# HexTo7seg.net
KiCad netlist of a schematic drawn in EAGLE
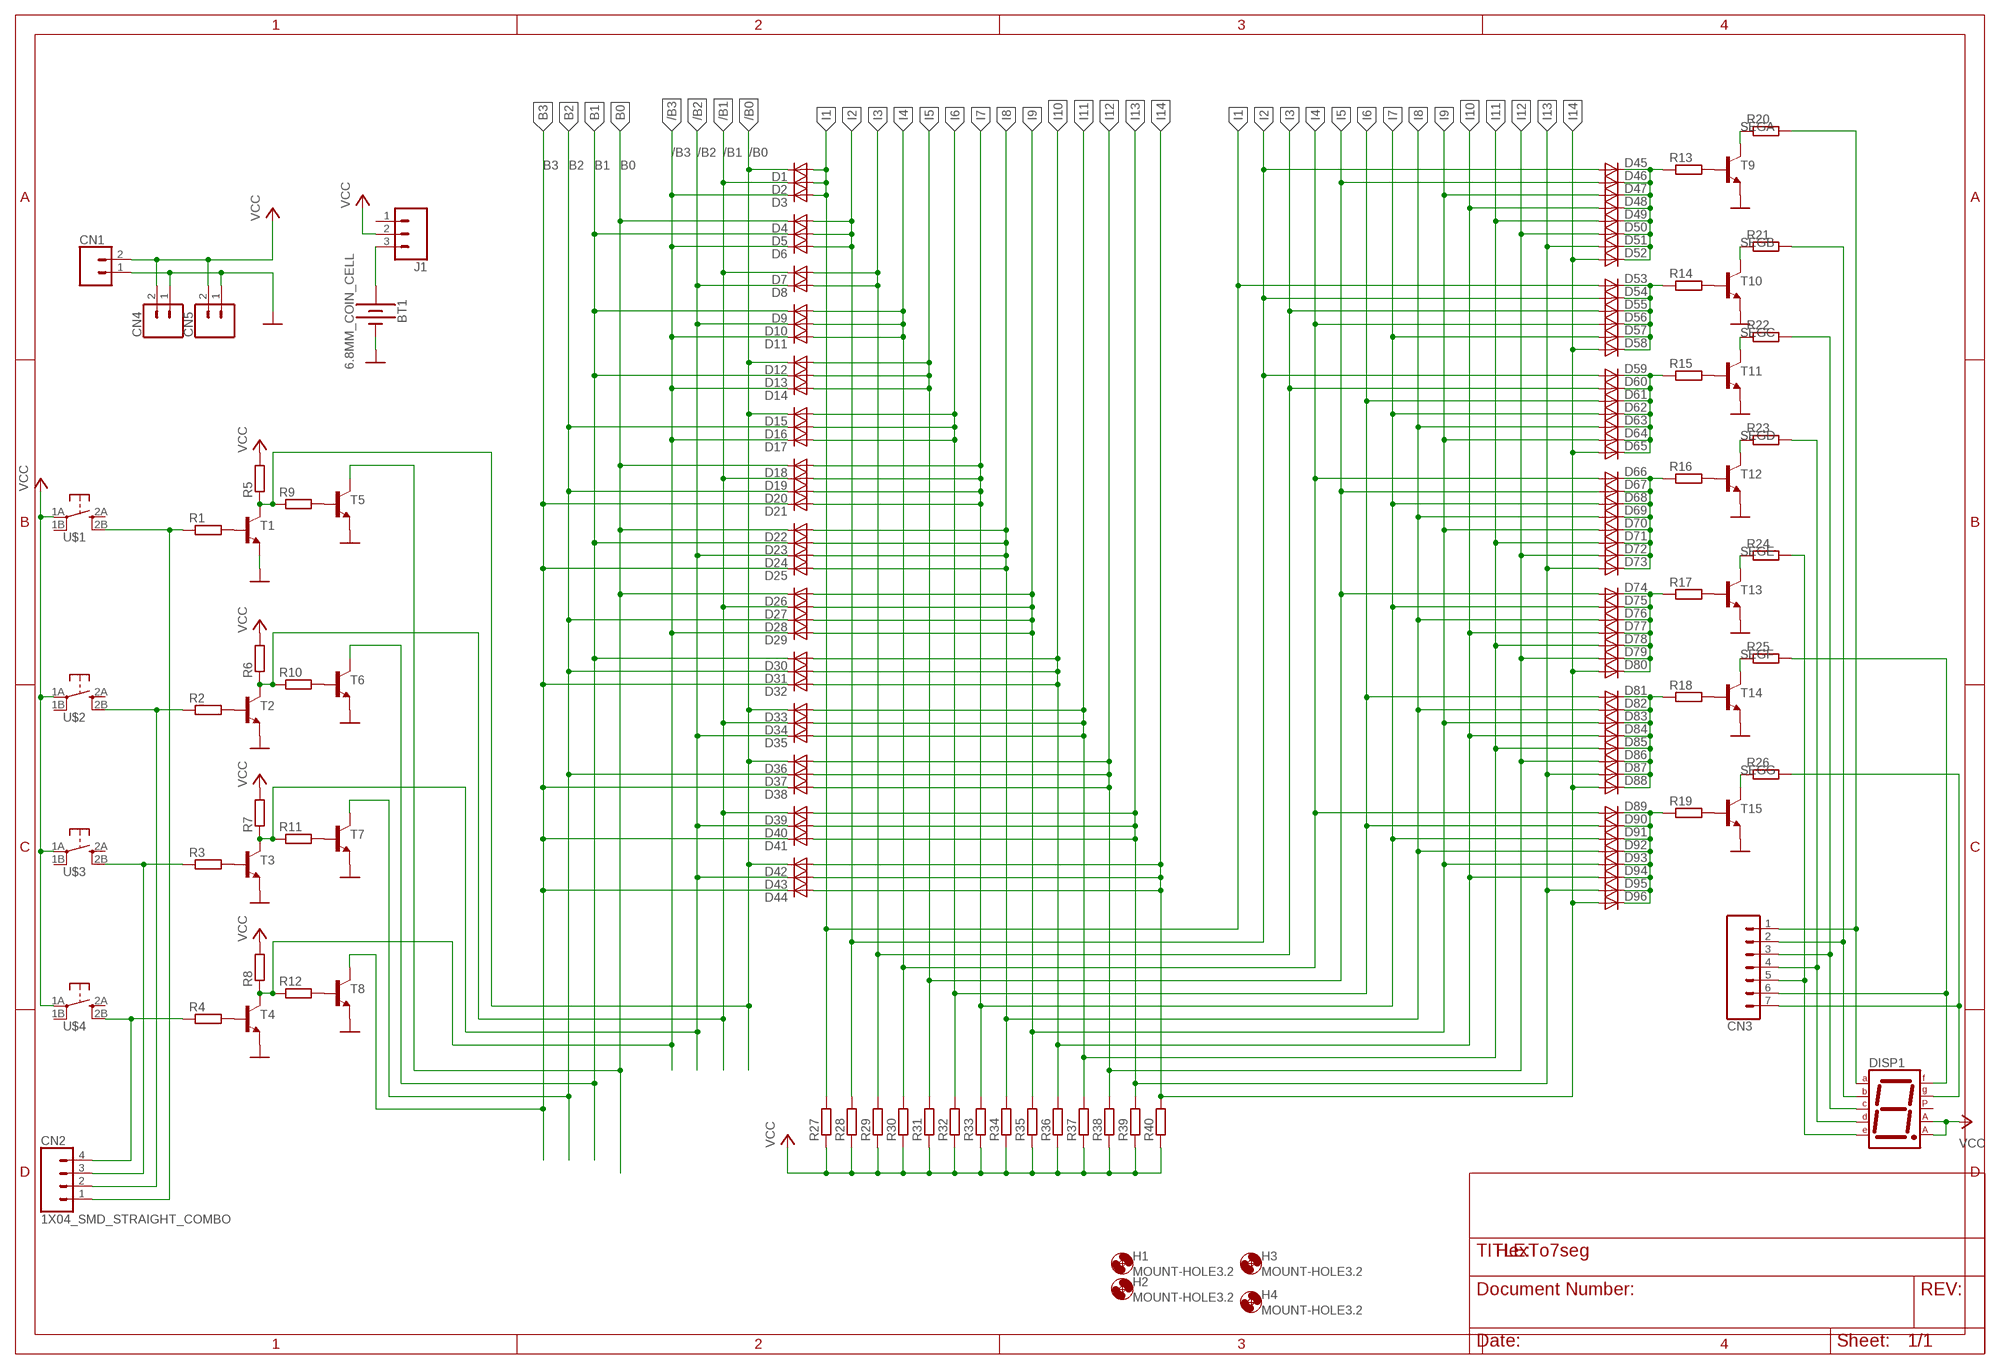
[diagram p0: schematic, sheet 1]

(export (version "E")
  (design (tool "Eeschema 10.0.6"))
  (components
    (comp (ref "BT1")
      (value "6.8MM_COIN_CELL")
      (footprint "eagle-import:BATTCOM_20MM_PTH")
      (libsource (lib "eagle-import") (part "BATTERY-20MM_PTH"))
    )
    (comp (ref "CN1")
      (value "CONN_02")
      (footprint "eagle-import:1X02")
      (libsource (lib "eagle-import") (part "CONN_02"))
    )
    (comp (ref "CN2")
      (value "1X04_SMD_STRAIGHT_COMBO")
      (footprint "eagle-import:1X04")
      (libsource (lib "eagle-import") (part "CONN_04"))
    )
    (comp (ref "CN3")
      (value "CONN_07")
      (footprint "eagle-import:1X07")
      (libsource (lib "eagle-import") (part "CONN_07"))
    )
    (comp (ref "CN4")
      (value "CONN_02")
      (footprint "eagle-import:1X02")
      (libsource (lib "eagle-import") (part "CONN_02"))
    )
    (comp (ref "CN5")
      (value "CONN_02")
      (footprint "eagle-import:1X02")
      (libsource (lib "eagle-import") (part "CONN_02"))
    )
    (comp (ref "D1")
      (value "SMALL_DIODEDO35-7")
      (footprint "eagle-import:DO35-7")
      (libsource (lib "eagle-import") (part "SMALL_DIODEDO35-7"))
    )
    (comp (ref "D2")
      (value "SMALL_DIODEDO35-7")
      (footprint "eagle-import:DO35-7")
      (libsource (lib "eagle-import") (part "SMALL_DIODEDO35-7"))
    )
    (comp (ref "D3")
      (value "SMALL_DIODEDO35-7")
      (footprint "eagle-import:DO35-7")
      (libsource (lib "eagle-import") (part "SMALL_DIODEDO35-7"))
    )
    (comp (ref "D4")
      (value "SMALL_DIODEDO35-7")
      (footprint "eagle-import:DO35-7")
      (libsource (lib "eagle-import") (part "SMALL_DIODEDO35-7"))
    )
    (comp (ref "D5")
      (value "SMALL_DIODEDO35-7")
      (footprint "eagle-import:DO35-7")
      (libsource (lib "eagle-import") (part "SMALL_DIODEDO35-7"))
    )
    (comp (ref "D6")
      (value "SMALL_DIODEDO35-7")
      (footprint "eagle-import:DO35-7")
      (libsource (lib "eagle-import") (part "SMALL_DIODEDO35-7"))
    )
    (comp (ref "D7")
      (value "SMALL_DIODEDO35-7")
      (footprint "eagle-import:DO35-7")
      (libsource (lib "eagle-import") (part "SMALL_DIODEDO35-7"))
    )
    (comp (ref "D8")
      (value "SMALL_DIODEDO35-7")
      (footprint "eagle-import:DO35-7")
      (libsource (lib "eagle-import") (part "SMALL_DIODEDO35-7"))
    )
    (comp (ref "D9")
      (value "SMALL_DIODEDO35-7")
      (footprint "eagle-import:DO35-7")
      (libsource (lib "eagle-import") (part "SMALL_DIODEDO35-7"))
    )
    (comp (ref "D10")
      (value "SMALL_DIODEDO35-7")
      (footprint "eagle-import:DO35-7")
      (libsource (lib "eagle-import") (part "SMALL_DIODEDO35-7"))
    )
    (comp (ref "D11")
      (value "SMALL_DIODEDO35-7")
      (footprint "eagle-import:DO35-7")
      (libsource (lib "eagle-import") (part "SMALL_DIODEDO35-7"))
    )
    (comp (ref "D12")
      (value "SMALL_DIODEDO35-7")
      (footprint "eagle-import:DO35-7")
      (libsource (lib "eagle-import") (part "SMALL_DIODEDO35-7"))
    )
    (comp (ref "D13")
      (value "SMALL_DIODEDO35-7")
      (footprint "eagle-import:DO35-7")
      (libsource (lib "eagle-import") (part "SMALL_DIODEDO35-7"))
    )
    (comp (ref "D14")
      (value "SMALL_DIODEDO35-7")
      (footprint "eagle-import:DO35-7")
      (libsource (lib "eagle-import") (part "SMALL_DIODEDO35-7"))
    )
    (comp (ref "D15")
      (value "SMALL_DIODEDO35-7")
      (footprint "eagle-import:DO35-7")
      (libsource (lib "eagle-import") (part "SMALL_DIODEDO35-7"))
    )
    (comp (ref "D16")
      (value "SMALL_DIODEDO35-7")
      (footprint "eagle-import:DO35-7")
      (libsource (lib "eagle-import") (part "SMALL_DIODEDO35-7"))
    )
    (comp (ref "D17")
      (value "SMALL_DIODEDO35-7")
      (footprint "eagle-import:DO35-7")
      (libsource (lib "eagle-import") (part "SMALL_DIODEDO35-7"))
    )
    (comp (ref "D18")
      (value "SMALL_DIODEDO35-7")
      (footprint "eagle-import:DO35-7")
      (libsource (lib "eagle-import") (part "SMALL_DIODEDO35-7"))
    )
    (comp (ref "D19")
      (value "SMALL_DIODEDO35-7")
      (footprint "eagle-import:DO35-7")
      (libsource (lib "eagle-import") (part "SMALL_DIODEDO35-7"))
    )
    (comp (ref "D20")
      (value "SMALL_DIODEDO35-7")
      (footprint "eagle-import:DO35-7")
      (libsource (lib "eagle-import") (part "SMALL_DIODEDO35-7"))
    )
    (comp (ref "D21")
      (value "SMALL_DIODEDO35-7")
      (footprint "eagle-import:DO35-7")
      (libsource (lib "eagle-import") (part "SMALL_DIODEDO35-7"))
    )
    (comp (ref "D22")
      (value "SMALL_DIODEDO35-7")
      (footprint "eagle-import:DO35-7")
      (libsource (lib "eagle-import") (part "SMALL_DIODEDO35-7"))
    )
    (comp (ref "D23")
      (value "SMALL_DIODEDO35-7")
      (footprint "eagle-import:DO35-7")
      (libsource (lib "eagle-import") (part "SMALL_DIODEDO35-7"))
    )
    (comp (ref "D24")
      (value "SMALL_DIODEDO35-7")
      (footprint "eagle-import:DO35-7")
      (libsource (lib "eagle-import") (part "SMALL_DIODEDO35-7"))
    )
    (comp (ref "D25")
      (value "SMALL_DIODEDO35-7")
      (footprint "eagle-import:DO35-7")
      (libsource (lib "eagle-import") (part "SMALL_DIODEDO35-7"))
    )
    (comp (ref "D26")
      (value "SMALL_DIODEDO35-7")
      (footprint "eagle-import:DO35-7")
      (libsource (lib "eagle-import") (part "SMALL_DIODEDO35-7"))
    )
    (comp (ref "D27")
      (value "SMALL_DIODEDO35-7")
      (footprint "eagle-import:DO35-7")
      (libsource (lib "eagle-import") (part "SMALL_DIODEDO35-7"))
    )
    (comp (ref "D28")
      (value "SMALL_DIODEDO35-7")
      (footprint "eagle-import:DO35-7")
      (libsource (lib "eagle-import") (part "SMALL_DIODEDO35-7"))
    )
    (comp (ref "D29")
      (value "SMALL_DIODEDO35-7")
      (footprint "eagle-import:DO35-7")
      (libsource (lib "eagle-import") (part "SMALL_DIODEDO35-7"))
    )
    (comp (ref "D30")
      (value "SMALL_DIODEDO35-7")
      (footprint "eagle-import:DO35-7")
      (libsource (lib "eagle-import") (part "SMALL_DIODEDO35-7"))
    )
    (comp (ref "D31")
      (value "SMALL_DIODEDO35-7")
      (footprint "eagle-import:DO35-7")
      (libsource (lib "eagle-import") (part "SMALL_DIODEDO35-7"))
    )
    (comp (ref "D32")
      (value "SMALL_DIODEDO35-7")
      (footprint "eagle-import:DO35-7")
      (libsource (lib "eagle-import") (part "SMALL_DIODEDO35-7"))
    )
    (comp (ref "D33")
      (value "SMALL_DIODEDO35-7")
      (footprint "eagle-import:DO35-7")
      (libsource (lib "eagle-import") (part "SMALL_DIODEDO35-7"))
    )
    (comp (ref "D34")
      (value "SMALL_DIODEDO35-7")
      (footprint "eagle-import:DO35-7")
      (libsource (lib "eagle-import") (part "SMALL_DIODEDO35-7"))
    )
    (comp (ref "D35")
      (value "SMALL_DIODEDO35-7")
      (footprint "eagle-import:DO35-7")
      (libsource (lib "eagle-import") (part "SMALL_DIODEDO35-7"))
    )
    (comp (ref "D36")
      (value "SMALL_DIODEDO35-7")
      (footprint "eagle-import:DO35-7")
      (libsource (lib "eagle-import") (part "SMALL_DIODEDO35-7"))
    )
    (comp (ref "D37")
      (value "SMALL_DIODEDO35-7")
      (footprint "eagle-import:DO35-7")
      (libsource (lib "eagle-import") (part "SMALL_DIODEDO35-7"))
    )
    (comp (ref "D38")
      (value "SMALL_DIODEDO35-7")
      (footprint "eagle-import:DO35-7")
      (libsource (lib "eagle-import") (part "SMALL_DIODEDO35-7"))
    )
    (comp (ref "D39")
      (value "SMALL_DIODEDO35-7")
      (footprint "eagle-import:DO35-7")
      (libsource (lib "eagle-import") (part "SMALL_DIODEDO35-7"))
    )
    (comp (ref "D40")
      (value "SMALL_DIODEDO35-7")
      (footprint "eagle-import:DO35-7")
      (libsource (lib "eagle-import") (part "SMALL_DIODEDO35-7"))
    )
    (comp (ref "D41")
      (value "SMALL_DIODEDO35-7")
      (footprint "eagle-import:DO35-7")
      (libsource (lib "eagle-import") (part "SMALL_DIODEDO35-7"))
    )
    (comp (ref "D42")
      (value "SMALL_DIODEDO35-7")
      (footprint "eagle-import:DO35-7")
      (libsource (lib "eagle-import") (part "SMALL_DIODEDO35-7"))
    )
    (comp (ref "D43")
      (value "SMALL_DIODEDO35-7")
      (footprint "eagle-import:DO35-7")
      (libsource (lib "eagle-import") (part "SMALL_DIODEDO35-7"))
    )
    (comp (ref "D44")
      (value "SMALL_DIODEDO35-7")
      (footprint "eagle-import:DO35-7")
      (libsource (lib "eagle-import") (part "SMALL_DIODEDO35-7"))
    )
    (comp (ref "D45")
      (value "SMALL_DIODEDO35-7")
      (footprint "eagle-import:DO35-7")
      (libsource (lib "eagle-import") (part "SMALL_DIODEDO35-7"))
    )
    (comp (ref "D46")
      (value "SMALL_DIODEDO35-7")
      (footprint "eagle-import:DO35-7")
      (libsource (lib "eagle-import") (part "SMALL_DIODEDO35-7"))
    )
    (comp (ref "D47")
      (value "SMALL_DIODEDO35-7")
      (footprint "eagle-import:DO35-7")
      (libsource (lib "eagle-import") (part "SMALL_DIODEDO35-7"))
    )
    (comp (ref "D48")
      (value "SMALL_DIODEDO35-7")
      (footprint "eagle-import:DO35-7")
      (libsource (lib "eagle-import") (part "SMALL_DIODEDO35-7"))
    )
    (comp (ref "D49")
      (value "SMALL_DIODEDO35-7")
      (footprint "eagle-import:DO35-7")
      (libsource (lib "eagle-import") (part "SMALL_DIODEDO35-7"))
    )
    (comp (ref "D50")
      (value "SMALL_DIODEDO35-7")
      (footprint "eagle-import:DO35-7")
      (libsource (lib "eagle-import") (part "SMALL_DIODEDO35-7"))
    )
    (comp (ref "D51")
      (value "SMALL_DIODEDO35-7")
      (footprint "eagle-import:DO35-7")
      (libsource (lib "eagle-import") (part "SMALL_DIODEDO35-7"))
    )
    (comp (ref "D52")
      (value "SMALL_DIODEDO35-7")
      (footprint "eagle-import:DO35-7")
      (libsource (lib "eagle-import") (part "SMALL_DIODEDO35-7"))
    )
    (comp (ref "D53")
      (value "SMALL_DIODEDO35-7")
      (footprint "eagle-import:DO35-7")
      (libsource (lib "eagle-import") (part "SMALL_DIODEDO35-7"))
    )
    (comp (ref "D54")
      (value "SMALL_DIODEDO35-7")
      (footprint "eagle-import:DO35-7")
      (libsource (lib "eagle-import") (part "SMALL_DIODEDO35-7"))
    )
    (comp (ref "D55")
      (value "SMALL_DIODEDO35-7")
      (footprint "eagle-import:DO35-7")
      (libsource (lib "eagle-import") (part "SMALL_DIODEDO35-7"))
    )
    (comp (ref "D56")
      (value "SMALL_DIODEDO35-7")
      (footprint "eagle-import:DO35-7")
      (libsource (lib "eagle-import") (part "SMALL_DIODEDO35-7"))
    )
    (comp (ref "D57")
      (value "SMALL_DIODEDO35-7")
      (footprint "eagle-import:DO35-7")
      (libsource (lib "eagle-import") (part "SMALL_DIODEDO35-7"))
    )
    (comp (ref "D58")
      (value "SMALL_DIODEDO35-7")
      (footprint "eagle-import:DO35-7")
      (libsource (lib "eagle-import") (part "SMALL_DIODEDO35-7"))
    )
    (comp (ref "D59")
      (value "SMALL_DIODEDO35-7")
      (footprint "eagle-import:DO35-7")
      (libsource (lib "eagle-import") (part "SMALL_DIODEDO35-7"))
    )
    (comp (ref "D60")
      (value "SMALL_DIODEDO35-7")
      (footprint "eagle-import:DO35-7")
      (libsource (lib "eagle-import") (part "SMALL_DIODEDO35-7"))
    )
    (comp (ref "D61")
      (value "SMALL_DIODEDO35-7")
      (footprint "eagle-import:DO35-7")
      (libsource (lib "eagle-import") (part "SMALL_DIODEDO35-7"))
    )
    (comp (ref "D62")
      (value "SMALL_DIODEDO35-7")
      (footprint "eagle-import:DO35-7")
      (libsource (lib "eagle-import") (part "SMALL_DIODEDO35-7"))
    )
    (comp (ref "D63")
      (value "SMALL_DIODEDO35-7")
      (footprint "eagle-import:DO35-7")
      (libsource (lib "eagle-import") (part "SMALL_DIODEDO35-7"))
    )
    (comp (ref "D64")
      (value "SMALL_DIODEDO35-7")
      (footprint "eagle-import:DO35-7")
      (libsource (lib "eagle-import") (part "SMALL_DIODEDO35-7"))
    )
    (comp (ref "D65")
      (value "SMALL_DIODEDO35-7")
      (footprint "eagle-import:DO35-7")
      (libsource (lib "eagle-import") (part "SMALL_DIODEDO35-7"))
    )
    (comp (ref "D66")
      (value "SMALL_DIODEDO35-7")
      (footprint "eagle-import:DO35-7")
      (libsource (lib "eagle-import") (part "SMALL_DIODEDO35-7"))
    )
    (comp (ref "D67")
      (value "SMALL_DIODEDO35-7")
      (footprint "eagle-import:DO35-7")
      (libsource (lib "eagle-import") (part "SMALL_DIODEDO35-7"))
    )
    (comp (ref "D68")
      (value "SMALL_DIODEDO35-7")
      (footprint "eagle-import:DO35-7")
      (libsource (lib "eagle-import") (part "SMALL_DIODEDO35-7"))
    )
    (comp (ref "D69")
      (value "SMALL_DIODEDO35-7")
      (footprint "eagle-import:DO35-7")
      (libsource (lib "eagle-import") (part "SMALL_DIODEDO35-7"))
    )
    (comp (ref "D70")
      (value "SMALL_DIODEDO35-7")
      (footprint "eagle-import:DO35-7")
      (libsource (lib "eagle-import") (part "SMALL_DIODEDO35-7"))
    )
    (comp (ref "D71")
      (value "SMALL_DIODEDO35-7")
      (footprint "eagle-import:DO35-7")
      (libsource (lib "eagle-import") (part "SMALL_DIODEDO35-7"))
    )
    (comp (ref "D72")
      (value "SMALL_DIODEDO35-7")
      (footprint "eagle-import:DO35-7")
      (libsource (lib "eagle-import") (part "SMALL_DIODEDO35-7"))
    )
    (comp (ref "D73")
      (value "SMALL_DIODEDO35-7")
      (footprint "eagle-import:DO35-7")
      (libsource (lib "eagle-import") (part "SMALL_DIODEDO35-7"))
    )
    (comp (ref "D74")
      (value "SMALL_DIODEDO35-7")
      (footprint "eagle-import:DO35-7")
      (libsource (lib "eagle-import") (part "SMALL_DIODEDO35-7"))
    )
    (comp (ref "D75")
      (value "SMALL_DIODEDO35-7")
      (footprint "eagle-import:DO35-7")
      (libsource (lib "eagle-import") (part "SMALL_DIODEDO35-7"))
    )
    (comp (ref "D76")
      (value "SMALL_DIODEDO35-7")
      (footprint "eagle-import:DO35-7")
      (libsource (lib "eagle-import") (part "SMALL_DIODEDO35-7"))
    )
    (comp (ref "D77")
      (value "SMALL_DIODEDO35-7")
      (footprint "eagle-import:DO35-7")
      (libsource (lib "eagle-import") (part "SMALL_DIODEDO35-7"))
    )
    (comp (ref "D78")
      (value "SMALL_DIODEDO35-7")
      (footprint "eagle-import:DO35-7")
      (libsource (lib "eagle-import") (part "SMALL_DIODEDO35-7"))
    )
    (comp (ref "D79")
      (value "SMALL_DIODEDO35-7")
      (footprint "eagle-import:DO35-7")
      (libsource (lib "eagle-import") (part "SMALL_DIODEDO35-7"))
    )
    (comp (ref "D80")
      (value "SMALL_DIODEDO35-7")
      (footprint "eagle-import:DO35-7")
      (libsource (lib "eagle-import") (part "SMALL_DIODEDO35-7"))
    )
    (comp (ref "D81")
      (value "SMALL_DIODEDO35-7")
      (footprint "eagle-import:DO35-7")
      (libsource (lib "eagle-import") (part "SMALL_DIODEDO35-7"))
    )
    (comp (ref "D82")
      (value "SMALL_DIODEDO35-7")
      (footprint "eagle-import:DO35-7")
      (libsource (lib "eagle-import") (part "SMALL_DIODEDO35-7"))
    )
    (comp (ref "D83")
      (value "SMALL_DIODEDO35-7")
      (footprint "eagle-import:DO35-7")
      (libsource (lib "eagle-import") (part "SMALL_DIODEDO35-7"))
    )
    (comp (ref "D84")
      (value "SMALL_DIODEDO35-7")
      (footprint "eagle-import:DO35-7")
      (libsource (lib "eagle-import") (part "SMALL_DIODEDO35-7"))
    )
    (comp (ref "D85")
      (value "SMALL_DIODEDO35-7")
      (footprint "eagle-import:DO35-7")
      (libsource (lib "eagle-import") (part "SMALL_DIODEDO35-7"))
    )
    (comp (ref "D86")
      (value "SMALL_DIODEDO35-7")
      (footprint "eagle-import:DO35-7")
      (libsource (lib "eagle-import") (part "SMALL_DIODEDO35-7"))
    )
    (comp (ref "D87")
      (value "SMALL_DIODEDO35-7")
      (footprint "eagle-import:DO35-7")
      (libsource (lib "eagle-import") (part "SMALL_DIODEDO35-7"))
    )
    (comp (ref "D88")
      (value "SMALL_DIODEDO35-7")
      (footprint "eagle-import:DO35-7")
      (libsource (lib "eagle-import") (part "SMALL_DIODEDO35-7"))
    )
    (comp (ref "D89")
      (value "SMALL_DIODEDO35-7")
      (footprint "eagle-import:DO35-7")
      (libsource (lib "eagle-import") (part "SMALL_DIODEDO35-7"))
    )
    (comp (ref "D90")
      (value "SMALL_DIODEDO35-7")
      (footprint "eagle-import:DO35-7")
      (libsource (lib "eagle-import") (part "SMALL_DIODEDO35-7"))
    )
    (comp (ref "D91")
      (value "SMALL_DIODEDO35-7")
      (footprint "eagle-import:DO35-7")
      (libsource (lib "eagle-import") (part "SMALL_DIODEDO35-7"))
    )
    (comp (ref "D92")
      (value "SMALL_DIODEDO35-7")
      (footprint "eagle-import:DO35-7")
      (libsource (lib "eagle-import") (part "SMALL_DIODEDO35-7"))
    )
    (comp (ref "D93")
      (value "SMALL_DIODEDO35-7")
      (footprint "eagle-import:DO35-7")
      (libsource (lib "eagle-import") (part "SMALL_DIODEDO35-7"))
    )
    (comp (ref "D94")
      (value "SMALL_DIODEDO35-7")
      (footprint "eagle-import:DO35-7")
      (libsource (lib "eagle-import") (part "SMALL_DIODEDO35-7"))
    )
    (comp (ref "D95")
      (value "SMALL_DIODEDO35-7")
      (footprint "eagle-import:DO35-7")
      (libsource (lib "eagle-import") (part "SMALL_DIODEDO35-7"))
    )
    (comp (ref "D96")
      (value "SMALL_DIODEDO35-7")
      (footprint "eagle-import:DO35-7")
      (libsource (lib "eagle-import") (part "SMALL_DIODEDO35-7"))
    )
    (comp (ref "DISP1")
      (value "7SEG-CA")
      (footprint "eagle-import:7SEG-13")
      (libsource (lib "eagle-import") (part "7SEG-CA"))
    )
    (comp (ref "H1")
      (value "MOUNT-HOLE3.2")
      (footprint "eagle-import:3,2")
      (libsource (lib "eagle-import") (part "MOUNT-HOLE3.2"))
    )
    (comp (ref "H2")
      (value "MOUNT-HOLE3.2")
      (footprint "eagle-import:3,2")
      (libsource (lib "eagle-import") (part "MOUNT-HOLE3.2"))
    )
    (comp (ref "H3")
      (value "MOUNT-HOLE3.2")
      (footprint "eagle-import:3,2")
      (libsource (lib "eagle-import") (part "MOUNT-HOLE3.2"))
    )
    (comp (ref "H4")
      (value "MOUNT-HOLE3.2")
      (footprint "eagle-import:3,2")
      (libsource (lib "eagle-import") (part "MOUNT-HOLE3.2"))
    )
    (comp (ref "J1")
      (value "CONN_03NP")
      (footprint "eagle-import:1X03NOSTOP")
      (libsource (lib "eagle-import") (part "CONN_03NP"))
    )
    (comp (ref "R1")
      (value "RESISTOR7MM")
      (footprint "eagle-import:7MM_RESISTOR")
      (libsource (lib "eagle-import") (part "RESISTOR7MM"))
    )
    (comp (ref "R2")
      (value "RESISTOR7MM")
      (footprint "eagle-import:7MM_RESISTOR")
      (libsource (lib "eagle-import") (part "RESISTOR7MM"))
    )
    (comp (ref "R3")
      (value "RESISTOR7MM")
      (footprint "eagle-import:7MM_RESISTOR")
      (libsource (lib "eagle-import") (part "RESISTOR7MM"))
    )
    (comp (ref "R4")
      (value "RESISTOR7MM")
      (footprint "eagle-import:7MM_RESISTOR")
      (libsource (lib "eagle-import") (part "RESISTOR7MM"))
    )
    (comp (ref "R5")
      (value "RESISTOR7MM")
      (footprint "eagle-import:7MM_RESISTOR")
      (libsource (lib "eagle-import") (part "RESISTOR7MM"))
    )
    (comp (ref "R6")
      (value "RESISTOR7MM")
      (footprint "eagle-import:7MM_RESISTOR")
      (libsource (lib "eagle-import") (part "RESISTOR7MM"))
    )
    (comp (ref "R7")
      (value "RESISTOR7MM")
      (footprint "eagle-import:7MM_RESISTOR")
      (libsource (lib "eagle-import") (part "RESISTOR7MM"))
    )
    (comp (ref "R8")
      (value "RESISTOR7MM")
      (footprint "eagle-import:7MM_RESISTOR")
      (libsource (lib "eagle-import") (part "RESISTOR7MM"))
    )
    (comp (ref "R9")
      (value "RESISTOR7MM")
      (footprint "eagle-import:7MM_RESISTOR")
      (libsource (lib "eagle-import") (part "RESISTOR7MM"))
    )
    (comp (ref "R10")
      (value "RESISTOR7MM")
      (footprint "eagle-import:7MM_RESISTOR")
      (libsource (lib "eagle-import") (part "RESISTOR7MM"))
    )
    (comp (ref "R11")
      (value "RESISTOR7MM")
      (footprint "eagle-import:7MM_RESISTOR")
      (libsource (lib "eagle-import") (part "RESISTOR7MM"))
    )
    (comp (ref "R12")
      (value "RESISTOR7MM")
      (footprint "eagle-import:7MM_RESISTOR")
      (libsource (lib "eagle-import") (part "RESISTOR7MM"))
    )
    (comp (ref "R13")
      (value "RESISTOR7MM")
      (footprint "eagle-import:7MM_RESISTOR")
      (libsource (lib "eagle-import") (part "RESISTOR7MM"))
    )
    (comp (ref "R14")
      (value "RESISTOR7MM")
      (footprint "eagle-import:7MM_RESISTOR")
      (libsource (lib "eagle-import") (part "RESISTOR7MM"))
    )
    (comp (ref "R15")
      (value "RESISTOR7MM")
      (footprint "eagle-import:7MM_RESISTOR")
      (libsource (lib "eagle-import") (part "RESISTOR7MM"))
    )
    (comp (ref "R16")
      (value "RESISTOR7MM")
      (footprint "eagle-import:7MM_RESISTOR")
      (libsource (lib "eagle-import") (part "RESISTOR7MM"))
    )
    (comp (ref "R17")
      (value "RESISTOR7MM")
      (footprint "eagle-import:7MM_RESISTOR")
      (libsource (lib "eagle-import") (part "RESISTOR7MM"))
    )
    (comp (ref "R18")
      (value "RESISTOR7MM")
      (footprint "eagle-import:7MM_RESISTOR")
      (libsource (lib "eagle-import") (part "RESISTOR7MM"))
    )
    (comp (ref "R19")
      (value "RESISTOR7MM")
      (footprint "eagle-import:7MM_RESISTOR")
      (libsource (lib "eagle-import") (part "RESISTOR7MM"))
    )
    (comp (ref "R20")
      (value "RESISTOR7MM")
      (footprint "eagle-import:7MM_RESISTOR")
      (libsource (lib "eagle-import") (part "RESISTOR7MM"))
    )
    (comp (ref "R21")
      (value "RESISTOR7MM")
      (footprint "eagle-import:7MM_RESISTOR")
      (libsource (lib "eagle-import") (part "RESISTOR7MM"))
    )
    (comp (ref "R22")
      (value "RESISTOR7MM")
      (footprint "eagle-import:7MM_RESISTOR")
      (libsource (lib "eagle-import") (part "RESISTOR7MM"))
    )
    (comp (ref "R23")
      (value "RESISTOR7MM")
      (footprint "eagle-import:7MM_RESISTOR")
      (libsource (lib "eagle-import") (part "RESISTOR7MM"))
    )
    (comp (ref "R24")
      (value "RESISTOR7MM")
      (footprint "eagle-import:7MM_RESISTOR")
      (libsource (lib "eagle-import") (part "RESISTOR7MM"))
    )
    (comp (ref "R25")
      (value "RESISTOR7MM")
      (footprint "eagle-import:7MM_RESISTOR")
      (libsource (lib "eagle-import") (part "RESISTOR7MM"))
    )
    (comp (ref "R26")
      (value "RESISTOR7MM")
      (footprint "eagle-import:7MM_RESISTOR")
      (libsource (lib "eagle-import") (part "RESISTOR7MM"))
    )
    (comp (ref "R27")
      (value "RESISTOR7MM")
      (footprint "eagle-import:7MM_RESISTOR")
      (libsource (lib "eagle-import") (part "RESISTOR7MM"))
    )
    (comp (ref "R28")
      (value "RESISTOR7MM")
      (footprint "eagle-import:7MM_RESISTOR")
      (libsource (lib "eagle-import") (part "RESISTOR7MM"))
    )
    (comp (ref "R29")
      (value "RESISTOR7MM")
      (footprint "eagle-import:7MM_RESISTOR")
      (libsource (lib "eagle-import") (part "RESISTOR7MM"))
    )
    (comp (ref "R30")
      (value "RESISTOR7MM")
      (footprint "eagle-import:7MM_RESISTOR")
      (libsource (lib "eagle-import") (part "RESISTOR7MM"))
    )
    (comp (ref "R31")
      (value "RESISTOR7MM")
      (footprint "eagle-import:7MM_RESISTOR")
      (libsource (lib "eagle-import") (part "RESISTOR7MM"))
    )
    (comp (ref "R32")
      (value "RESISTOR7MM")
      (footprint "eagle-import:7MM_RESISTOR")
      (libsource (lib "eagle-import") (part "RESISTOR7MM"))
    )
    (comp (ref "R33")
      (value "RESISTOR7MM")
      (footprint "eagle-import:7MM_RESISTOR")
      (libsource (lib "eagle-import") (part "RESISTOR7MM"))
    )
    (comp (ref "R34")
      (value "RESISTOR7MM")
      (footprint "eagle-import:7MM_RESISTOR")
      (libsource (lib "eagle-import") (part "RESISTOR7MM"))
    )
    (comp (ref "R35")
      (value "RESISTOR7MM")
      (footprint "eagle-import:7MM_RESISTOR")
      (libsource (lib "eagle-import") (part "RESISTOR7MM"))
    )
    (comp (ref "R36")
      (value "RESISTOR7MM")
      (footprint "eagle-import:7MM_RESISTOR")
      (libsource (lib "eagle-import") (part "RESISTOR7MM"))
    )
    (comp (ref "R37")
      (value "RESISTOR7MM")
      (footprint "eagle-import:7MM_RESISTOR")
      (libsource (lib "eagle-import") (part "RESISTOR7MM"))
    )
    (comp (ref "R38")
      (value "RESISTOR7MM")
      (footprint "eagle-import:7MM_RESISTOR")
      (libsource (lib "eagle-import") (part "RESISTOR7MM"))
    )
    (comp (ref "R39")
      (value "RESISTOR7MM")
      (footprint "eagle-import:7MM_RESISTOR")
      (libsource (lib "eagle-import") (part "RESISTOR7MM"))
    )
    (comp (ref "R40")
      (value "RESISTOR7MM")
      (footprint "eagle-import:7MM_RESISTOR")
      (libsource (lib "eagle-import") (part "RESISTOR7MM"))
    )
    (comp (ref "T1")
      (value "BC547B-NPN-TO92-CBE")
      (footprint "eagle-import:TO92-CBE")
      (libsource (lib "eagle-import") (part "-NPN-TO92-CBEBC547B"))
    )
    (comp (ref "T2")
      (value "BC547B-NPN-TO92-CBE")
      (footprint "eagle-import:TO92-CBE")
      (libsource (lib "eagle-import") (part "-NPN-TO92-CBEBC547B"))
    )
    (comp (ref "T3")
      (value "BC547B-NPN-TO92-CBE")
      (footprint "eagle-import:TO92-CBE")
      (libsource (lib "eagle-import") (part "-NPN-TO92-CBEBC547B"))
    )
    (comp (ref "T4")
      (value "BC547B-NPN-TO92-CBE")
      (footprint "eagle-import:TO92-CBE")
      (libsource (lib "eagle-import") (part "-NPN-TO92-CBEBC547B"))
    )
    (comp (ref "T5")
      (value "BC547B-NPN-TO92-CBE")
      (footprint "eagle-import:TO92-CBE")
      (libsource (lib "eagle-import") (part "-NPN-TO92-CBEBC547B"))
    )
    (comp (ref "T6")
      (value "BC547B-NPN-TO92-CBE")
      (footprint "eagle-import:TO92-CBE")
      (libsource (lib "eagle-import") (part "-NPN-TO92-CBEBC547B"))
    )
    (comp (ref "T7")
      (value "BC547B-NPN-TO92-CBE")
      (footprint "eagle-import:TO92-CBE")
      (libsource (lib "eagle-import") (part "-NPN-TO92-CBEBC547B"))
    )
    (comp (ref "T8")
      (value "BC547B-NPN-TO92-CBE")
      (footprint "eagle-import:TO92-CBE")
      (libsource (lib "eagle-import") (part "-NPN-TO92-CBEBC547B"))
    )
    (comp (ref "T9")
      (value "BC547B-NPN-TO92-CBE")
      (footprint "eagle-import:TO92-CBE")
      (libsource (lib "eagle-import") (part "-NPN-TO92-CBEBC547B"))
    )
    (comp (ref "T10")
      (value "BC547B-NPN-TO92-CBE")
      (footprint "eagle-import:TO92-CBE")
      (libsource (lib "eagle-import") (part "-NPN-TO92-CBEBC547B"))
    )
    (comp (ref "T11")
      (value "BC547B-NPN-TO92-CBE")
      (footprint "eagle-import:TO92-CBE")
      (libsource (lib "eagle-import") (part "-NPN-TO92-CBEBC547B"))
    )
    (comp (ref "T12")
      (value "BC547B-NPN-TO92-CBE")
      (footprint "eagle-import:TO92-CBE")
      (libsource (lib "eagle-import") (part "-NPN-TO92-CBEBC547B"))
    )
    (comp (ref "T13")
      (value "BC547B-NPN-TO92-CBE")
      (footprint "eagle-import:TO92-CBE")
      (libsource (lib "eagle-import") (part "-NPN-TO92-CBEBC547B"))
    )
    (comp (ref "T14")
      (value "BC547B-NPN-TO92-CBE")
      (footprint "eagle-import:TO92-CBE")
      (libsource (lib "eagle-import") (part "-NPN-TO92-CBEBC547B"))
    )
    (comp (ref "T15")
      (value "BC547B-NPN-TO92-CBE")
      (footprint "eagle-import:TO92-CBE")
      (libsource (lib "eagle-import") (part "-NPN-TO92-CBEBC547B"))
    )
    (comp (ref "U$1")
      (value "TACTILETACT-6X6-PTH")
      (footprint "eagle-import:TACTILE-PTH")
      (libsource (lib "eagle-import") (part "TACTILETACT-6X6-PTH"))
    )
    (comp (ref "U$2")
      (value "TACTILETACT-6X6-PTH")
      (footprint "eagle-import:TACTILE-PTH")
      (libsource (lib "eagle-import") (part "TACTILETACT-6X6-PTH"))
    )
    (comp (ref "U$3")
      (value "TACTILETACT-6X6-PTH")
      (footprint "eagle-import:TACTILE-PTH")
      (libsource (lib "eagle-import") (part "TACTILETACT-6X6-PTH"))
    )
    (comp (ref "U$4")
      (value "TACTILETACT-6X6-PTH")
      (footprint "eagle-import:TACTILE-PTH")
      (libsource (lib "eagle-import") (part "TACTILETACT-6X6-PTH"))
    )
  )
  (nets
    (net (code "1") (name "/SEGA") (class "Default")
      (node (ref "R20") (pin "1") (pinfunction "1_1") (pintype "passive"))
      (node (ref "T9") (pin "C") (pinfunction "C_C") (pintype "passive"))
    )
    (net (code "2") (name "/SEGB") (class "Default")
      (node (ref "R21") (pin "1") (pinfunction "1_1") (pintype "passive"))
      (node (ref "T10") (pin "C") (pinfunction "C_C") (pintype "passive"))
    )
    (net (code "3") (name "/SEGC") (class "Default")
      (node (ref "R22") (pin "1") (pinfunction "1_1") (pintype "passive"))
      (node (ref "T11") (pin "C") (pinfunction "C_C") (pintype "passive"))
    )
    (net (code "4") (name "/SEGD") (class "Default")
      (node (ref "R23") (pin "1") (pinfunction "1_1") (pintype "passive"))
      (node (ref "T12") (pin "C") (pinfunction "C_C") (pintype "passive"))
    )
    (net (code "5") (name "/SEGE") (class "Default")
      (node (ref "R24") (pin "1") (pinfunction "1_1") (pintype "passive"))
      (node (ref "T13") (pin "C") (pinfunction "C_C") (pintype "passive"))
    )
    (net (code "6") (name "/SEGF") (class "Default")
      (node (ref "R25") (pin "1") (pinfunction "1_1") (pintype "passive"))
      (node (ref "T14") (pin "C") (pinfunction "C_C") (pintype "passive"))
    )
    (net (code "7") (name "/SEGG") (class "Default")
      (node (ref "R26") (pin "1") (pinfunction "1_1") (pintype "passive"))
      (node (ref "T15") (pin "C") (pinfunction "C_C") (pintype "passive"))
    )
    (net (code "8") (name "B0") (class "Default")
      (node (ref "D18") (pin "C") (pinfunction "C_C") (pintype "passive"))
      (node (ref "D22") (pin "C") (pinfunction "C_C") (pintype "passive"))
      (node (ref "D26") (pin "C") (pinfunction "C_C") (pintype "passive"))
      (node (ref "D4") (pin "C") (pinfunction "C_C") (pintype "passive"))
      (node (ref "T5") (pin "C") (pinfunction "C_C") (pintype "passive"))
    )
    (net (code "9") (name "B1") (class "Default")
      (node (ref "D13") (pin "C") (pinfunction "C_C") (pintype "passive"))
      (node (ref "D23") (pin "C") (pinfunction "C_C") (pintype "passive"))
      (node (ref "D30") (pin "C") (pinfunction "C_C") (pintype "passive"))
      (node (ref "D5") (pin "C") (pinfunction "C_C") (pintype "passive"))
      (node (ref "D9") (pin "C") (pinfunction "C_C") (pintype "passive"))
      (node (ref "T6") (pin "C") (pinfunction "C_C") (pintype "passive"))
    )
    (net (code "10") (name "B2") (class "Default")
      (node (ref "D16") (pin "C") (pinfunction "C_C") (pintype "passive"))
      (node (ref "D20") (pin "C") (pinfunction "C_C") (pintype "passive"))
      (node (ref "D28") (pin "C") (pinfunction "C_C") (pintype "passive"))
      (node (ref "D31") (pin "C") (pinfunction "C_C") (pintype "passive"))
      (node (ref "D37") (pin "C") (pinfunction "C_C") (pintype "passive"))
      (node (ref "T7") (pin "C") (pinfunction "C_C") (pintype "passive"))
    )
    (net (code "11") (name "B3") (class "Default")
      (node (ref "D21") (pin "C") (pinfunction "C_C") (pintype "passive"))
      (node (ref "D25") (pin "C") (pinfunction "C_C") (pintype "passive"))
      (node (ref "D32") (pin "C") (pinfunction "C_C") (pintype "passive"))
      (node (ref "D38") (pin "C") (pinfunction "C_C") (pintype "passive"))
      (node (ref "D41") (pin "C") (pinfunction "C_C") (pintype "passive"))
      (node (ref "D44") (pin "C") (pinfunction "C_C") (pintype "passive"))
      (node (ref "T8") (pin "C") (pinfunction "C_C") (pintype "passive"))
    )
    (net (code "12") (name "GND") (class "Default")
      (node (ref "BT1") (pin "2") (pinfunction "-_2") (pintype "power_in"))
      (node (ref "CN1") (pin "1") (pinfunction "1_1") (pintype "passive"))
      (node (ref "CN4") (pin "1") (pinfunction "1_1") (pintype "passive"))
      (node (ref "CN5") (pin "1") (pinfunction "1_1") (pintype "passive"))
      (node (ref "T1") (pin "E") (pinfunction "E_E") (pintype "passive"))
      (node (ref "T10") (pin "E") (pinfunction "E_E") (pintype "passive"))
      (node (ref "T11") (pin "E") (pinfunction "E_E") (pintype "passive"))
      (node (ref "T12") (pin "E") (pinfunction "E_E") (pintype "passive"))
      (node (ref "T13") (pin "E") (pinfunction "E_E") (pintype "passive"))
      (node (ref "T14") (pin "E") (pinfunction "E_E") (pintype "passive"))
      (node (ref "T15") (pin "E") (pinfunction "E_E") (pintype "passive"))
      (node (ref "T2") (pin "E") (pinfunction "E_E") (pintype "passive"))
      (node (ref "T3") (pin "E") (pinfunction "E_E") (pintype "passive"))
      (node (ref "T4") (pin "E") (pinfunction "E_E") (pintype "passive"))
      (node (ref "T5") (pin "E") (pinfunction "E_E") (pintype "passive"))
      (node (ref "T6") (pin "E") (pinfunction "E_E") (pintype "passive"))
      (node (ref "T7") (pin "E") (pinfunction "E_E") (pintype "passive"))
      (node (ref "T8") (pin "E") (pinfunction "E_E") (pintype "passive"))
      (node (ref "T9") (pin "E") (pinfunction "E_E") (pintype "passive"))
    )
    (net (code "13") (name "I1") (class "Default")
      (node (ref "D1") (pin "A") (pinfunction "A_A") (pintype "passive"))
      (node (ref "D2") (pin "A") (pinfunction "A_A") (pintype "passive"))
      (node (ref "D3") (pin "A") (pinfunction "A_A") (pintype "passive"))
      (node (ref "D53") (pin "A") (pinfunction "A_A") (pintype "passive"))
      (node (ref "R27") (pin "2") (pinfunction "2_2") (pintype "passive"))
    )
    (net (code "14") (name "I2") (class "Default")
      (node (ref "D4") (pin "A") (pinfunction "A_A") (pintype "passive"))
      (node (ref "D45") (pin "A") (pinfunction "A_A") (pintype "passive"))
      (node (ref "D5") (pin "A") (pinfunction "A_A") (pintype "passive"))
      (node (ref "D54") (pin "A") (pinfunction "A_A") (pintype "passive"))
      (node (ref "D59") (pin "A") (pinfunction "A_A") (pintype "passive"))
      (node (ref "D6") (pin "A") (pinfunction "A_A") (pintype "passive"))
      (node (ref "R28") (pin "2") (pinfunction "2_2") (pintype "passive"))
    )
    (net (code "15") (name "I3") (class "Default")
      (node (ref "D55") (pin "A") (pinfunction "A_A") (pintype "passive"))
      (node (ref "D60") (pin "A") (pinfunction "A_A") (pintype "passive"))
      (node (ref "D7") (pin "A") (pinfunction "A_A") (pintype "passive"))
      (node (ref "D8") (pin "A") (pinfunction "A_A") (pintype "passive"))
      (node (ref "R29") (pin "2") (pinfunction "2_2") (pintype "passive"))
    )
    (net (code "16") (name "I4") (class "Default")
      (node (ref "D10") (pin "A") (pinfunction "A_A") (pintype "passive"))
      (node (ref "D11") (pin "A") (pinfunction "A_A") (pintype "passive"))
      (node (ref "D56") (pin "A") (pinfunction "A_A") (pintype "passive"))
      (node (ref "D66") (pin "A") (pinfunction "A_A") (pintype "passive"))
      (node (ref "D89") (pin "A") (pinfunction "A_A") (pintype "passive"))
      (node (ref "D9") (pin "A") (pinfunction "A_A") (pintype "passive"))
      (node (ref "R30") (pin "2") (pinfunction "2_2") (pintype "passive"))
    )
    (net (code "17") (name "I5") (class "Default")
      (node (ref "D12") (pin "A") (pinfunction "A_A") (pintype "passive"))
      (node (ref "D13") (pin "A") (pinfunction "A_A") (pintype "passive"))
      (node (ref "D14") (pin "A") (pinfunction "A_A") (pintype "passive"))
      (node (ref "D46") (pin "A") (pinfunction "A_A") (pintype "passive"))
      (node (ref "D67") (pin "A") (pinfunction "A_A") (pintype "passive"))
      (node (ref "D74") (pin "A") (pinfunction "A_A") (pintype "passive"))
      (node (ref "R31") (pin "2") (pinfunction "2_2") (pintype "passive"))
    )
    (net (code "18") (name "I6") (class "Default")
      (node (ref "D15") (pin "A") (pinfunction "A_A") (pintype "passive"))
      (node (ref "D16") (pin "A") (pinfunction "A_A") (pintype "passive"))
      (node (ref "D17") (pin "A") (pinfunction "A_A") (pintype "passive"))
      (node (ref "D61") (pin "A") (pinfunction "A_A") (pintype "passive"))
      (node (ref "D81") (pin "A") (pinfunction "A_A") (pintype "passive"))
      (node (ref "D90") (pin "A") (pinfunction "A_A") (pintype "passive"))
      (node (ref "R32") (pin "2") (pinfunction "2_2") (pintype "passive"))
    )
    (net (code "19") (name "I7") (class "Default")
      (node (ref "D18") (pin "A") (pinfunction "A_A") (pintype "passive"))
      (node (ref "D19") (pin "A") (pinfunction "A_A") (pintype "passive"))
      (node (ref "D20") (pin "A") (pinfunction "A_A") (pintype "passive"))
      (node (ref "D21") (pin "A") (pinfunction "A_A") (pintype "passive"))
      (node (ref "D57") (pin "A") (pinfunction "A_A") (pintype "passive"))
      (node (ref "D62") (pin "A") (pinfunction "A_A") (pintype "passive"))
      (node (ref "D68") (pin "A") (pinfunction "A_A") (pintype "passive"))
      (node (ref "D75") (pin "A") (pinfunction "A_A") (pintype "passive"))
      (node (ref "D91") (pin "A") (pinfunction "A_A") (pintype "passive"))
      (node (ref "R33") (pin "2") (pinfunction "2_2") (pintype "passive"))
    )
    (net (code "20") (name "I8") (class "Default")
      (node (ref "D22") (pin "A") (pinfunction "A_A") (pintype "passive"))
      (node (ref "D23") (pin "A") (pinfunction "A_A") (pintype "passive"))
      (node (ref "D24") (pin "A") (pinfunction "A_A") (pintype "passive"))
      (node (ref "D25") (pin "A") (pinfunction "A_A") (pintype "passive"))
      (node (ref "D63") (pin "A") (pinfunction "A_A") (pintype "passive"))
      (node (ref "D69") (pin "A") (pinfunction "A_A") (pintype "passive"))
      (node (ref "D76") (pin "A") (pinfunction "A_A") (pintype "passive"))
      (node (ref "D82") (pin "A") (pinfunction "A_A") (pintype "passive"))
      (node (ref "D92") (pin "A") (pinfunction "A_A") (pintype "passive"))
      (node (ref "R34") (pin "2") (pinfunction "2_2") (pintype "passive"))
    )
    (net (code "21") (name "I9") (class "Default")
      (node (ref "D26") (pin "A") (pinfunction "A_A") (pintype "passive"))
      (node (ref "D27") (pin "A") (pinfunction "A_A") (pintype "passive"))
      (node (ref "D28") (pin "A") (pinfunction "A_A") (pintype "passive"))
      (node (ref "D29") (pin "A") (pinfunction "A_A") (pintype "passive"))
      (node (ref "D47") (pin "A") (pinfunction "A_A") (pintype "passive"))
      (node (ref "D64") (pin "A") (pinfunction "A_A") (pintype "passive"))
      (node (ref "D70") (pin "A") (pinfunction "A_A") (pintype "passive"))
      (node (ref "D83") (pin "A") (pinfunction "A_A") (pintype "passive"))
      (node (ref "D93") (pin "A") (pinfunction "A_A") (pintype "passive"))
      (node (ref "R35") (pin "2") (pinfunction "2_2") (pintype "passive"))
    )
    (net (code "22") (name "I10") (class "Default")
      (node (ref "D30") (pin "A") (pinfunction "A_A") (pintype "passive"))
      (node (ref "D31") (pin "A") (pinfunction "A_A") (pintype "passive"))
      (node (ref "D32") (pin "A") (pinfunction "A_A") (pintype "passive"))
      (node (ref "D48") (pin "A") (pinfunction "A_A") (pintype "passive"))
      (node (ref "D77") (pin "A") (pinfunction "A_A") (pintype "passive"))
      (node (ref "D84") (pin "A") (pinfunction "A_A") (pintype "passive"))
      (node (ref "D94") (pin "A") (pinfunction "A_A") (pintype "passive"))
      (node (ref "R36") (pin "2") (pinfunction "2_2") (pintype "passive"))
    )
    (net (code "23") (name "I11") (class "Default")
      (node (ref "D33") (pin "A") (pinfunction "A_A") (pintype "passive"))
      (node (ref "D34") (pin "A") (pinfunction "A_A") (pintype "passive"))
      (node (ref "D35") (pin "A") (pinfunction "A_A") (pintype "passive"))
      (node (ref "D49") (pin "A") (pinfunction "A_A") (pintype "passive"))
      (node (ref "D71") (pin "A") (pinfunction "A_A") (pintype "passive"))
      (node (ref "D78") (pin "A") (pinfunction "A_A") (pintype "passive"))
      (node (ref "D85") (pin "A") (pinfunction "A_A") (pintype "passive"))
      (node (ref "R37") (pin "2") (pinfunction "2_2") (pintype "passive"))
    )
    (net (code "24") (name "I12") (class "Default")
      (node (ref "D36") (pin "A") (pinfunction "A_A") (pintype "passive"))
      (node (ref "D37") (pin "A") (pinfunction "A_A") (pintype "passive"))
      (node (ref "D38") (pin "A") (pinfunction "A_A") (pintype "passive"))
      (node (ref "D50") (pin "A") (pinfunction "A_A") (pintype "passive"))
      (node (ref "D72") (pin "A") (pinfunction "A_A") (pintype "passive"))
      (node (ref "D79") (pin "A") (pinfunction "A_A") (pintype "passive"))
      (node (ref "D86") (pin "A") (pinfunction "A_A") (pintype "passive"))
      (node (ref "R38") (pin "2") (pinfunction "2_2") (pintype "passive"))
    )
    (net (code "25") (name "I13") (class "Default")
      (node (ref "D39") (pin "A") (pinfunction "A_A") (pintype "passive"))
      (node (ref "D40") (pin "A") (pinfunction "A_A") (pintype "passive"))
      (node (ref "D41") (pin "A") (pinfunction "A_A") (pintype "passive"))
      (node (ref "D51") (pin "A") (pinfunction "A_A") (pintype "passive"))
      (node (ref "D73") (pin "A") (pinfunction "A_A") (pintype "passive"))
      (node (ref "D87") (pin "A") (pinfunction "A_A") (pintype "passive"))
      (node (ref "D95") (pin "A") (pinfunction "A_A") (pintype "passive"))
      (node (ref "R39") (pin "2") (pinfunction "2_2") (pintype "passive"))
    )
    (net (code "26") (name "I14") (class "Default")
      (node (ref "D42") (pin "A") (pinfunction "A_A") (pintype "passive"))
      (node (ref "D43") (pin "A") (pinfunction "A_A") (pintype "passive"))
      (node (ref "D44") (pin "A") (pinfunction "A_A") (pintype "passive"))
      (node (ref "D52") (pin "A") (pinfunction "A_A") (pintype "passive"))
      (node (ref "D58") (pin "A") (pinfunction "A_A") (pintype "passive"))
      (node (ref "D65") (pin "A") (pinfunction "A_A") (pintype "passive"))
      (node (ref "D80") (pin "A") (pinfunction "A_A") (pintype "passive"))
      (node (ref "D88") (pin "A") (pinfunction "A_A") (pintype "passive"))
      (node (ref "D96") (pin "A") (pinfunction "A_A") (pintype "passive"))
      (node (ref "R40") (pin "2") (pinfunction "2_2") (pintype "passive"))
    )
    (net (code "27") (name "Net-(BT1-+)") (class "Default")
      (node (ref "BT1") (pin "1") (pinfunction "+_1") (pintype "power_in"))
      (node (ref "J1") (pin "3") (pinfunction "3_3") (pintype "passive"))
    )
    (net (code "28") (name "Net-(CN2-Pad1)") (class "Default")
      (node (ref "CN2") (pin "1") (pinfunction "1_1") (pintype "passive"))
      (node (ref "R1") (pin "1") (pinfunction "1_1") (pintype "passive"))
      (node (ref "U$1") (pin "2B") (pinfunction "2B_2B") (pintype "passive"))
    )
    (net (code "29") (name "Net-(CN2-Pad2)") (class "Default")
      (node (ref "CN2") (pin "2") (pinfunction "2_2") (pintype "passive"))
      (node (ref "R2") (pin "1") (pinfunction "1_1") (pintype "passive"))
      (node (ref "U$2") (pin "2B") (pinfunction "2B_2B") (pintype "passive"))
    )
    (net (code "30") (name "Net-(CN2-Pad3)") (class "Default")
      (node (ref "CN2") (pin "3") (pinfunction "3_3") (pintype "passive"))
      (node (ref "R3") (pin "1") (pinfunction "1_1") (pintype "passive"))
      (node (ref "U$3") (pin "2B") (pinfunction "2B_2B") (pintype "passive"))
    )
    (net (code "31") (name "Net-(CN2-Pad4)") (class "Default")
      (node (ref "CN2") (pin "4") (pinfunction "4_4") (pintype "passive"))
      (node (ref "R4") (pin "1") (pinfunction "1_1") (pintype "passive"))
      (node (ref "U$4") (pin "2B") (pinfunction "2B_2B") (pintype "passive"))
    )
    (net (code "32") (name "Net-(D45-PadC)") (class "Default")
      (node (ref "D45") (pin "C") (pinfunction "C_C") (pintype "passive"))
      (node (ref "D46") (pin "C") (pinfunction "C_C") (pintype "passive"))
      (node (ref "D47") (pin "C") (pinfunction "C_C") (pintype "passive"))
      (node (ref "D48") (pin "C") (pinfunction "C_C") (pintype "passive"))
      (node (ref "D49") (pin "C") (pinfunction "C_C") (pintype "passive"))
      (node (ref "D50") (pin "C") (pinfunction "C_C") (pintype "passive"))
      (node (ref "D51") (pin "C") (pinfunction "C_C") (pintype "passive"))
      (node (ref "D52") (pin "C") (pinfunction "C_C") (pintype "passive"))
      (node (ref "R13") (pin "1") (pinfunction "1_1") (pintype "passive"))
    )
    (net (code "33") (name "Net-(D53-PadC)") (class "Default")
      (node (ref "D53") (pin "C") (pinfunction "C_C") (pintype "passive"))
      (node (ref "D54") (pin "C") (pinfunction "C_C") (pintype "passive"))
      (node (ref "D55") (pin "C") (pinfunction "C_C") (pintype "passive"))
      (node (ref "D56") (pin "C") (pinfunction "C_C") (pintype "passive"))
      (node (ref "D57") (pin "C") (pinfunction "C_C") (pintype "passive"))
      (node (ref "D58") (pin "C") (pinfunction "C_C") (pintype "passive"))
      (node (ref "R14") (pin "1") (pinfunction "1_1") (pintype "passive"))
    )
    (net (code "34") (name "Net-(D59-PadC)") (class "Default")
      (node (ref "D59") (pin "C") (pinfunction "C_C") (pintype "passive"))
      (node (ref "D60") (pin "C") (pinfunction "C_C") (pintype "passive"))
      (node (ref "D61") (pin "C") (pinfunction "C_C") (pintype "passive"))
      (node (ref "D62") (pin "C") (pinfunction "C_C") (pintype "passive"))
      (node (ref "D63") (pin "C") (pinfunction "C_C") (pintype "passive"))
      (node (ref "D64") (pin "C") (pinfunction "C_C") (pintype "passive"))
      (node (ref "D65") (pin "C") (pinfunction "C_C") (pintype "passive"))
      (node (ref "R15") (pin "1") (pinfunction "1_1") (pintype "passive"))
    )
    (net (code "35") (name "Net-(D66-PadC)") (class "Default")
      (node (ref "D66") (pin "C") (pinfunction "C_C") (pintype "passive"))
      (node (ref "D67") (pin "C") (pinfunction "C_C") (pintype "passive"))
      (node (ref "D68") (pin "C") (pinfunction "C_C") (pintype "passive"))
      (node (ref "D69") (pin "C") (pinfunction "C_C") (pintype "passive"))
      (node (ref "D70") (pin "C") (pinfunction "C_C") (pintype "passive"))
      (node (ref "D71") (pin "C") (pinfunction "C_C") (pintype "passive"))
      (node (ref "D72") (pin "C") (pinfunction "C_C") (pintype "passive"))
      (node (ref "D73") (pin "C") (pinfunction "C_C") (pintype "passive"))
      (node (ref "R16") (pin "1") (pinfunction "1_1") (pintype "passive"))
    )
    (net (code "36") (name "Net-(D74-PadC)") (class "Default")
      (node (ref "D74") (pin "C") (pinfunction "C_C") (pintype "passive"))
      (node (ref "D75") (pin "C") (pinfunction "C_C") (pintype "passive"))
      (node (ref "D76") (pin "C") (pinfunction "C_C") (pintype "passive"))
      (node (ref "D77") (pin "C") (pinfunction "C_C") (pintype "passive"))
      (node (ref "D78") (pin "C") (pinfunction "C_C") (pintype "passive"))
      (node (ref "D79") (pin "C") (pinfunction "C_C") (pintype "passive"))
      (node (ref "D80") (pin "C") (pinfunction "C_C") (pintype "passive"))
      (node (ref "R17") (pin "1") (pinfunction "1_1") (pintype "passive"))
    )
    (net (code "37") (name "Net-(D81-PadC)") (class "Default")
      (node (ref "D81") (pin "C") (pinfunction "C_C") (pintype "passive"))
      (node (ref "D82") (pin "C") (pinfunction "C_C") (pintype "passive"))
      (node (ref "D83") (pin "C") (pinfunction "C_C") (pintype "passive"))
      (node (ref "D84") (pin "C") (pinfunction "C_C") (pintype "passive"))
      (node (ref "D85") (pin "C") (pinfunction "C_C") (pintype "passive"))
      (node (ref "D86") (pin "C") (pinfunction "C_C") (pintype "passive"))
      (node (ref "D87") (pin "C") (pinfunction "C_C") (pintype "passive"))
      (node (ref "D88") (pin "C") (pinfunction "C_C") (pintype "passive"))
      (node (ref "R18") (pin "1") (pinfunction "1_1") (pintype "passive"))
    )
    (net (code "38") (name "Net-(D89-PadC)") (class "Default")
      (node (ref "D89") (pin "C") (pinfunction "C_C") (pintype "passive"))
      (node (ref "D90") (pin "C") (pinfunction "C_C") (pintype "passive"))
      (node (ref "D91") (pin "C") (pinfunction "C_C") (pintype "passive"))
      (node (ref "D92") (pin "C") (pinfunction "C_C") (pintype "passive"))
      (node (ref "D93") (pin "C") (pinfunction "C_C") (pintype "passive"))
      (node (ref "D94") (pin "C") (pinfunction "C_C") (pintype "passive"))
      (node (ref "D95") (pin "C") (pinfunction "C_C") (pintype "passive"))
      (node (ref "D96") (pin "C") (pinfunction "C_C") (pintype "passive"))
      (node (ref "R19") (pin "1") (pinfunction "1_1") (pintype "passive"))
    )
    (net (code "39") (name "Net-(DISP1-A)") (class "Default")
      (node (ref "CN3") (pin "1") (pinfunction "1_1") (pintype "passive"))
      (node (ref "DISP1") (pin "7") (pinfunction "A_7") (pintype "passive"))
      (node (ref "R20") (pin "2") (pinfunction "2_2") (pintype "passive"))
    )
    (net (code "40") (name "Net-(DISP1-B)") (class "Default")
      (node (ref "CN3") (pin "2") (pinfunction "2_2") (pintype "passive"))
      (node (ref "DISP1") (pin "6") (pinfunction "B_6") (pintype "passive"))
      (node (ref "R21") (pin "2") (pinfunction "2_2") (pintype "passive"))
    )
    (net (code "41") (name "Net-(DISP1-C)") (class "Default")
      (node (ref "CN3") (pin "3") (pinfunction "3_3") (pintype "passive"))
      (node (ref "DISP1") (pin "4") (pinfunction "C_4") (pintype "passive"))
      (node (ref "R22") (pin "2") (pinfunction "2_2") (pintype "passive"))
    )
    (net (code "42") (name "Net-(DISP1-D)") (class "Default")
      (node (ref "CN3") (pin "4") (pinfunction "4_4") (pintype "passive"))
      (node (ref "DISP1") (pin "2") (pinfunction "D_2") (pintype "passive"))
      (node (ref "R23") (pin "2") (pinfunction "2_2") (pintype "passive"))
    )
    (net (code "43") (name "Net-(DISP1-E)") (class "Default")
      (node (ref "CN3") (pin "5") (pinfunction "5_5") (pintype "passive"))
      (node (ref "DISP1") (pin "1") (pinfunction "E_1") (pintype "passive"))
      (node (ref "R24") (pin "2") (pinfunction "2_2") (pintype "passive"))
    )
    (net (code "44") (name "Net-(DISP1-F)") (class "Default")
      (node (ref "CN3") (pin "6") (pinfunction "6_6") (pintype "passive"))
      (node (ref "DISP1") (pin "9") (pinfunction "F_9") (pintype "passive"))
      (node (ref "R25") (pin "2") (pinfunction "2_2") (pintype "passive"))
    )
    (net (code "45") (name "Net-(DISP1-G)") (class "Default")
      (node (ref "CN3") (pin "7") (pinfunction "7_7") (pintype "passive"))
      (node (ref "DISP1") (pin "10") (pinfunction "G_10") (pintype "passive"))
      (node (ref "R26") (pin "2") (pinfunction "2_2") (pintype "passive"))
    )
    (net (code "46") (name "Net-(R1-Pad2)") (class "Default")
      (node (ref "R1") (pin "2") (pinfunction "2_2") (pintype "passive"))
      (node (ref "T1") (pin "B") (pinfunction "B_B") (pintype "passive"))
    )
    (net (code "47") (name "Net-(R2-Pad2)") (class "Default")
      (node (ref "R2") (pin "2") (pinfunction "2_2") (pintype "passive"))
      (node (ref "T2") (pin "B") (pinfunction "B_B") (pintype "passive"))
    )
    (net (code "48") (name "Net-(R3-Pad2)") (class "Default")
      (node (ref "R3") (pin "2") (pinfunction "2_2") (pintype "passive"))
      (node (ref "T3") (pin "B") (pinfunction "B_B") (pintype "passive"))
    )
    (net (code "49") (name "Net-(R4-Pad2)") (class "Default")
      (node (ref "R4") (pin "2") (pinfunction "2_2") (pintype "passive"))
      (node (ref "T4") (pin "B") (pinfunction "B_B") (pintype "passive"))
    )
    (net (code "50") (name "Net-(R9-Pad2)") (class "Default")
      (node (ref "R9") (pin "2") (pinfunction "2_2") (pintype "passive"))
      (node (ref "T5") (pin "B") (pinfunction "B_B") (pintype "passive"))
    )
    (net (code "51") (name "Net-(R10-Pad2)") (class "Default")
      (node (ref "R10") (pin "2") (pinfunction "2_2") (pintype "passive"))
      (node (ref "T6") (pin "B") (pinfunction "B_B") (pintype "passive"))
    )
    (net (code "52") (name "Net-(R11-Pad2)") (class "Default")
      (node (ref "R11") (pin "2") (pinfunction "2_2") (pintype "passive"))
      (node (ref "T7") (pin "B") (pinfunction "B_B") (pintype "passive"))
    )
    (net (code "53") (name "Net-(R12-Pad2)") (class "Default")
      (node (ref "R12") (pin "2") (pinfunction "2_2") (pintype "passive"))
      (node (ref "T8") (pin "B") (pinfunction "B_B") (pintype "passive"))
    )
    (net (code "54") (name "Net-(R13-Pad2)") (class "Default")
      (node (ref "R13") (pin "2") (pinfunction "2_2") (pintype "passive"))
      (node (ref "T9") (pin "B") (pinfunction "B_B") (pintype "passive"))
    )
    (net (code "55") (name "Net-(R14-Pad2)") (class "Default")
      (node (ref "R14") (pin "2") (pinfunction "2_2") (pintype "passive"))
      (node (ref "T10") (pin "B") (pinfunction "B_B") (pintype "passive"))
    )
    (net (code "56") (name "Net-(R15-Pad2)") (class "Default")
      (node (ref "R15") (pin "2") (pinfunction "2_2") (pintype "passive"))
      (node (ref "T11") (pin "B") (pinfunction "B_B") (pintype "passive"))
    )
    (net (code "57") (name "Net-(R16-Pad2)") (class "Default")
      (node (ref "R16") (pin "2") (pinfunction "2_2") (pintype "passive"))
      (node (ref "T12") (pin "B") (pinfunction "B_B") (pintype "passive"))
    )
    (net (code "58") (name "Net-(R17-Pad2)") (class "Default")
      (node (ref "R17") (pin "2") (pinfunction "2_2") (pintype "passive"))
      (node (ref "T13") (pin "B") (pinfunction "B_B") (pintype "passive"))
    )
    (net (code "59") (name "Net-(R18-Pad2)") (class "Default")
      (node (ref "R18") (pin "2") (pinfunction "2_2") (pintype "passive"))
      (node (ref "T14") (pin "B") (pinfunction "B_B") (pintype "passive"))
    )
    (net (code "60") (name "Net-(R19-Pad2)") (class "Default")
      (node (ref "R19") (pin "2") (pinfunction "2_2") (pintype "passive"))
      (node (ref "T15") (pin "B") (pinfunction "B_B") (pintype "passive"))
    )
    (net (code "61") (name "VCC") (class "Default")
      (node (ref "CN1") (pin "2") (pinfunction "2_2") (pintype "passive"))
      (node (ref "CN4") (pin "2") (pinfunction "2_2") (pintype "passive"))
      (node (ref "CN5") (pin "2") (pinfunction "2_2") (pintype "passive"))
      (node (ref "DISP1") (pin "3") (pinfunction "CA1_3") (pintype "passive"))
      (node (ref "DISP1") (pin "8") (pinfunction "CA2_8") (pintype "passive"))
      (node (ref "J1") (pin "2") (pinfunction "2_2") (pintype "passive"))
      (node (ref "R27") (pin "1") (pinfunction "1_1") (pintype "passive"))
      (node (ref "R28") (pin "1") (pinfunction "1_1") (pintype "passive"))
      (node (ref "R29") (pin "1") (pinfunction "1_1") (pintype "passive"))
      (node (ref "R30") (pin "1") (pinfunction "1_1") (pintype "passive"))
      (node (ref "R31") (pin "1") (pinfunction "1_1") (pintype "passive"))
      (node (ref "R32") (pin "1") (pinfunction "1_1") (pintype "passive"))
      (node (ref "R33") (pin "1") (pinfunction "1_1") (pintype "passive"))
      (node (ref "R34") (pin "1") (pinfunction "1_1") (pintype "passive"))
      (node (ref "R35") (pin "1") (pinfunction "1_1") (pintype "passive"))
      (node (ref "R36") (pin "1") (pinfunction "1_1") (pintype "passive"))
      (node (ref "R37") (pin "1") (pinfunction "1_1") (pintype "passive"))
      (node (ref "R38") (pin "1") (pinfunction "1_1") (pintype "passive"))
      (node (ref "R39") (pin "1") (pinfunction "1_1") (pintype "passive"))
      (node (ref "R40") (pin "1") (pinfunction "1_1") (pintype "passive"))
      (node (ref "R5") (pin "2") (pinfunction "2_2") (pintype "passive"))
      (node (ref "R6") (pin "2") (pinfunction "2_2") (pintype "passive"))
      (node (ref "R7") (pin "2") (pinfunction "2_2") (pintype "passive"))
      (node (ref "R8") (pin "2") (pinfunction "2_2") (pintype "passive"))
      (node (ref "U$1") (pin "1A") (pinfunction "1A_1A") (pintype "passive"))
      (node (ref "U$2") (pin "1A") (pinfunction "1A_1A") (pintype "passive"))
      (node (ref "U$3") (pin "1A") (pinfunction "1A_1A") (pintype "passive"))
      (node (ref "U$4") (pin "1A") (pinfunction "1A_1A") (pintype "passive"))
    )
    (net (code "62") (name "unconnected-(DISP1-DP-Pad5)") (class "Default")
      (node (ref "DISP1") (pin "5") (pinfunction "DP_5") (pintype "passive"))
    )
    (net (code "63") (name "unconnected-(J1-Pad1)") (class "Default")
      (node (ref "J1") (pin "1") (pinfunction "1_1") (pintype "passive"))
    )
    (net (code "64") (name "unconnected-(U$1-Pad1B)") (class "Default")
      (node (ref "U$1") (pin "1B") (pinfunction "1B_1B") (pintype "passive"))
    )
    (net (code "65") (name "unconnected-(U$1-Pad2A)") (class "Default")
      (node (ref "U$1") (pin "2A") (pinfunction "2A_2A") (pintype "passive"))
    )
    (net (code "66") (name "unconnected-(U$2-Pad1B)") (class "Default")
      (node (ref "U$2") (pin "1B") (pinfunction "1B_1B") (pintype "passive"))
    )
    (net (code "67") (name "unconnected-(U$2-Pad2A)") (class "Default")
      (node (ref "U$2") (pin "2A") (pinfunction "2A_2A") (pintype "passive"))
    )
    (net (code "68") (name "unconnected-(U$3-Pad1B)") (class "Default")
      (node (ref "U$3") (pin "1B") (pinfunction "1B_1B") (pintype "passive"))
    )
    (net (code "69") (name "unconnected-(U$3-Pad2A)") (class "Default")
      (node (ref "U$3") (pin "2A") (pinfunction "2A_2A") (pintype "passive"))
    )
    (net (code "70") (name "unconnected-(U$4-Pad1B)") (class "Default")
      (node (ref "U$4") (pin "1B") (pinfunction "1B_1B") (pintype "passive"))
    )
    (net (code "71") (name "unconnected-(U$4-Pad2A)") (class "Default")
      (node (ref "U$4") (pin "2A") (pinfunction "2A_2A") (pintype "passive"))
    )
    (net (code "72") (name "{slash}B0") (class "Default")
      (node (ref "D1") (pin "C") (pinfunction "C_C") (pintype "passive"))
      (node (ref "D12") (pin "C") (pinfunction "C_C") (pintype "passive"))
      (node (ref "D15") (pin "C") (pinfunction "C_C") (pintype "passive"))
      (node (ref "D33") (pin "C") (pinfunction "C_C") (pintype "passive"))
      (node (ref "D36") (pin "C") (pinfunction "C_C") (pintype "passive"))
      (node (ref "D42") (pin "C") (pinfunction "C_C") (pintype "passive"))
      (node (ref "R5") (pin "1") (pinfunction "1_1") (pintype "passive"))
      (node (ref "R9") (pin "1") (pinfunction "1_1") (pintype "passive"))
      (node (ref "T1") (pin "C") (pinfunction "C_C") (pintype "passive"))
    )
    (net (code "73") (name "{slash}B1") (class "Default")
      (node (ref "D19") (pin "C") (pinfunction "C_C") (pintype "passive"))
      (node (ref "D2") (pin "C") (pinfunction "C_C") (pintype "passive"))
      (node (ref "D27") (pin "C") (pinfunction "C_C") (pintype "passive"))
      (node (ref "D34") (pin "C") (pinfunction "C_C") (pintype "passive"))
      (node (ref "D39") (pin "C") (pinfunction "C_C") (pintype "passive"))
      (node (ref "D7") (pin "C") (pinfunction "C_C") (pintype "passive"))
      (node (ref "R10") (pin "1") (pinfunction "1_1") (pintype "passive"))
      (node (ref "R6") (pin "1") (pinfunction "1_1") (pintype "passive"))
      (node (ref "T2") (pin "C") (pinfunction "C_C") (pintype "passive"))
    )
    (net (code "74") (name "{slash}B2") (class "Default")
      (node (ref "D10") (pin "C") (pinfunction "C_C") (pintype "passive"))
      (node (ref "D24") (pin "C") (pinfunction "C_C") (pintype "passive"))
      (node (ref "D35") (pin "C") (pinfunction "C_C") (pintype "passive"))
      (node (ref "D40") (pin "C") (pinfunction "C_C") (pintype "passive"))
      (node (ref "D43") (pin "C") (pinfunction "C_C") (pintype "passive"))
      (node (ref "D8") (pin "C") (pinfunction "C_C") (pintype "passive"))
      (node (ref "R11") (pin "1") (pinfunction "1_1") (pintype "passive"))
      (node (ref "R7") (pin "1") (pinfunction "1_1") (pintype "passive"))
      (node (ref "T3") (pin "C") (pinfunction "C_C") (pintype "passive"))
    )
    (net (code "75") (name "{slash}B3") (class "Default")
      (node (ref "D11") (pin "C") (pinfunction "C_C") (pintype "passive"))
      (node (ref "D14") (pin "C") (pinfunction "C_C") (pintype "passive"))
      (node (ref "D17") (pin "C") (pinfunction "C_C") (pintype "passive"))
      (node (ref "D29") (pin "C") (pinfunction "C_C") (pintype "passive"))
      (node (ref "D3") (pin "C") (pinfunction "C_C") (pintype "passive"))
      (node (ref "D6") (pin "C") (pinfunction "C_C") (pintype "passive"))
      (node (ref "R12") (pin "1") (pinfunction "1_1") (pintype "passive"))
      (node (ref "R8") (pin "1") (pinfunction "1_1") (pintype "passive"))
      (node (ref "T4") (pin "C") (pinfunction "C_C") (pintype "passive"))
    )
  )
)
